# bat_mini_drby_2018.net
KiCad netlist of a schematic drawn in EAGLE
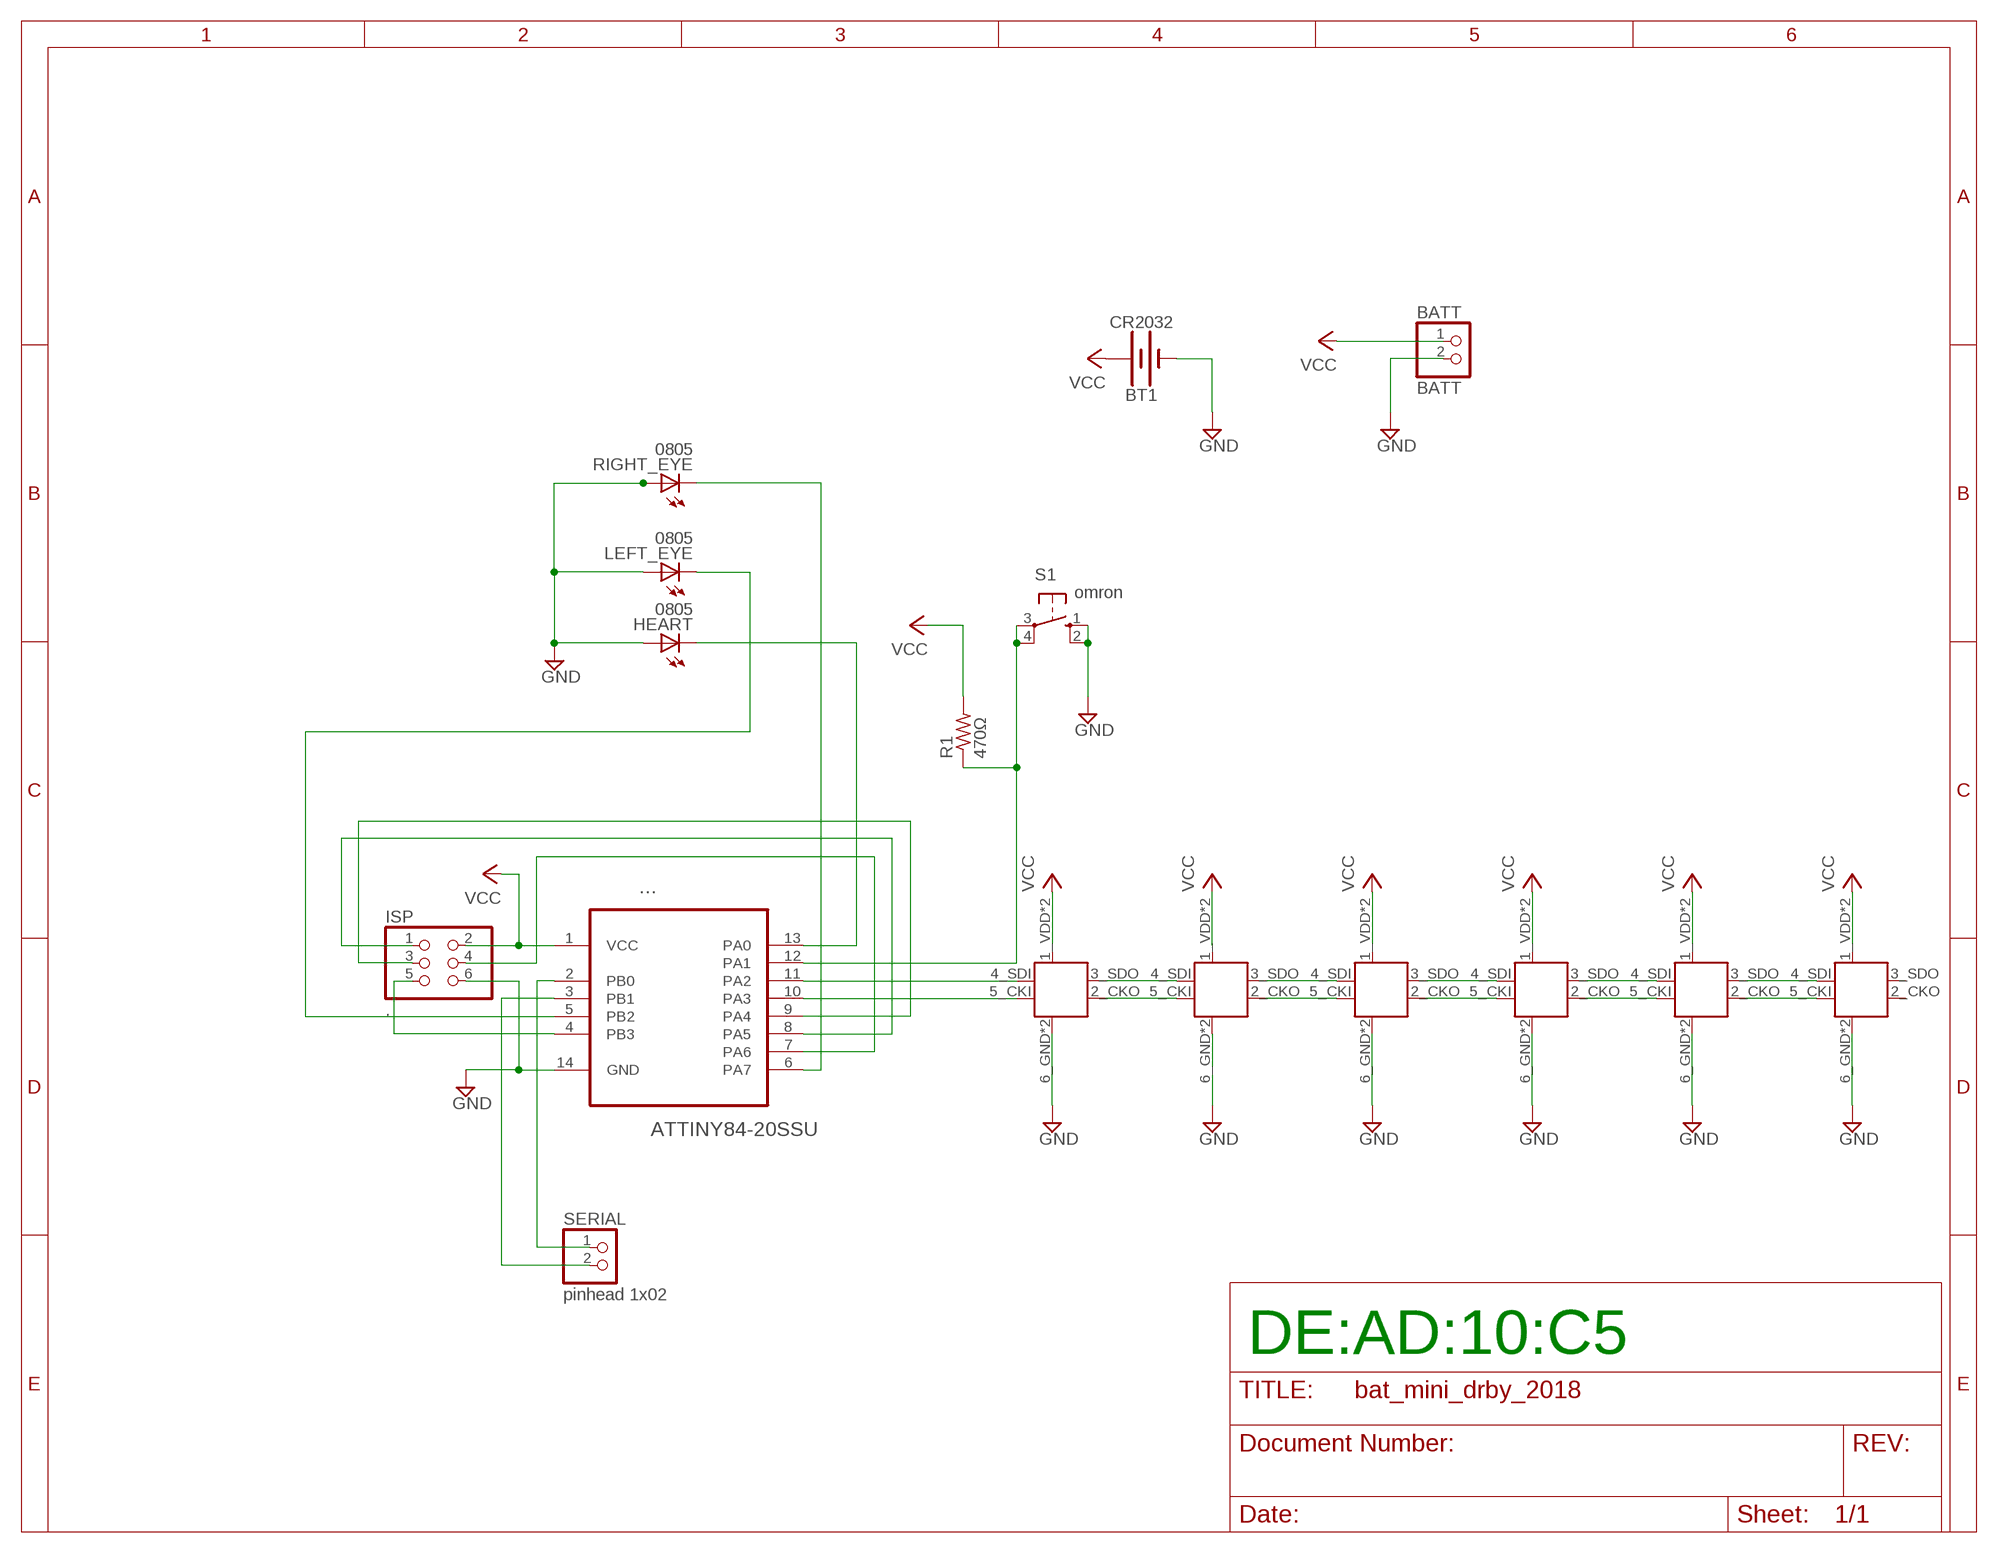
[diagram p0: schematic, sheet 1]

(export (version "E")
  (design (tool "Eeschema 10.0.6"))
  (components
    (comp (ref "...")
      (value "ATTINY84-20SSU")
      (footprint "eagle-import:SOIC127P600X175-14N")
      (libsource (lib "eagle-import") (part "ATTINY84-20SSU"))
    )
    (comp (ref "BATT")
      (value "BATT")
      (footprint "eagle-import:1X02")
      (libsource (lib "eagle-import") (part "PINHD-1X2"))
    )
    (comp (ref "BT1")
      (value "CR2032")
      (footprint "eagle-import:BATTCON_20MM_4LEGS")
      (libsource (lib "eagle-import") (part "BATTERY-20MM_SMD_4LEGS"))
    )
    (comp (ref "HEART")
      (value "0805")
      (footprint "eagle-import:CHIP-LED0805")
      (libsource (lib "eagle-import") (part "LEDCHIP-LED0805"))
    )
    (comp (ref "ISP")
      (value ".")
      (footprint "eagle-import:2X03")
      (libsource (lib "eagle-import") (part "PINHD-2X3"))
    )
    (comp (ref "LEFT_EYE")
      (value "0805")
      (footprint "eagle-import:CHIP-LED0805")
      (libsource (lib "eagle-import") (part "LEDCHIP-LED0805"))
    )
    (comp (ref "R1")
      (value "470Ω")
      (footprint "eagle-import:R0805")
      (libsource (lib "eagle-import") (part "R-US_R0805"))
    )
    (comp (ref "RIGHT_EYE")
      (value "0805")
      (footprint "eagle-import:CHIP-LED0805")
      (libsource (lib "eagle-import") (part "LEDCHIP-LED0805"))
    )
    (comp (ref "S1")
      (value "omron")
      (footprint "eagle-import:B3F-10XX")
      (fields (field (name "MPN") "B3F-1000"))
      (libsource (lib "eagle-import") (part "10-XX"))
    )
    (comp (ref "SERIAL")
      (value "pinhead 1x02")
      (footprint "eagle-import:1X02")
      (libsource (lib "eagle-import") (part "PINHD-1X2"))
    )
    (comp (ref "U$4")
      (value "APA102")
      (footprint "eagle-import:APA102-2020")
      (libsource (lib "eagle-import") (part "APA102"))
    )
    (comp (ref "U$8")
      (value "APA102")
      (footprint "eagle-import:APA102-2020")
      (libsource (lib "eagle-import") (part "APA102"))
    )
    (comp (ref "U$9")
      (value "APA102")
      (footprint "eagle-import:APA102-2020")
      (libsource (lib "eagle-import") (part "APA102"))
    )
    (comp (ref "U$10")
      (value "APA102")
      (footprint "eagle-import:APA102-2020")
      (libsource (lib "eagle-import") (part "APA102"))
    )
    (comp (ref "U$11")
      (value "APA102")
      (footprint "eagle-import:APA102-2020")
      (libsource (lib "eagle-import") (part "APA102"))
    )
    (comp (ref "U$12")
      (value "APA102")
      (footprint "eagle-import:APA102-2020")
      (libsource (lib "eagle-import") (part "APA102"))
    )
  )
  (nets
    (net (code "1") (name "GND") (class "Default")
      (node (ref "...") (pin "14") (pinfunction "GND_14") (pintype "passive"))
      (node (ref "BATT") (pin "2") (pinfunction "2_2") (pintype "passive"))
      (node (ref "BT1") (pin "NEGATIVE") (pinfunction "-_NEGATIVE") (pintype "power_in"))
      (node (ref "HEART") (pin "A") (pinfunction "A_A") (pintype "passive"))
      (node (ref "ISP") (pin "6") (pinfunction "6_6") (pintype "passive"))
      (node (ref "LEFT_EYE") (pin "A") (pinfunction "A_A") (pintype "passive"))
      (node (ref "RIGHT_EYE") (pin "A") (pinfunction "A_A") (pintype "passive"))
      (node (ref "S1") (pin "1") (pinfunction "S_1") (pintype "passive"))
      (node (ref "S1") (pin "2") (pinfunction "S1_2") (pintype "passive"))
      (node (ref "U$10") (pin "6_GND") (pinfunction "GND_6_GND") (pintype "power_in"))
      (node (ref "U$10") (pin "GNDPAD") (pinfunction "GND_GNDPAD") (pintype "power_in"))
      (node (ref "U$11") (pin "6_GND") (pinfunction "GND_6_GND") (pintype "power_in"))
      (node (ref "U$11") (pin "GNDPAD") (pinfunction "GND_GNDPAD") (pintype "power_in"))
      (node (ref "U$12") (pin "6_GND") (pinfunction "GND_6_GND") (pintype "power_in"))
      (node (ref "U$12") (pin "GNDPAD") (pinfunction "GND_GNDPAD") (pintype "power_in"))
      (node (ref "U$4") (pin "6_GND") (pinfunction "GND_6_GND") (pintype "power_in"))
      (node (ref "U$4") (pin "GNDPAD") (pinfunction "GND_GNDPAD") (pintype "power_in"))
      (node (ref "U$8") (pin "6_GND") (pinfunction "GND_6_GND") (pintype "power_in"))
      (node (ref "U$8") (pin "GNDPAD") (pinfunction "GND_GNDPAD") (pintype "power_in"))
      (node (ref "U$9") (pin "6_GND") (pinfunction "GND_6_GND") (pintype "power_in"))
      (node (ref "U$9") (pin "GNDPAD") (pinfunction "GND_GNDPAD") (pintype "power_in"))
    )
    (net (code "2") (name "Net-(...-PA0)") (class "Default")
      (node (ref "...") (pin "13") (pinfunction "PA0_13") (pintype "bidirectional"))
      (node (ref "HEART") (pin "C") (pinfunction "C_C") (pintype "passive"))
    )
    (net (code "3") (name "Net-(...-PA1)") (class "Default")
      (node (ref "...") (pin "12") (pinfunction "PA1_12") (pintype "bidirectional"))
      (node (ref "R1") (pin "1") (pinfunction "1_1") (pintype "passive"))
      (node (ref "S1") (pin "3") (pinfunction "P_3") (pintype "passive"))
      (node (ref "S1") (pin "4") (pinfunction "P1_4") (pintype "passive"))
    )
    (net (code "4") (name "Net-(...-PA2)") (class "Default")
      (node (ref "...") (pin "11") (pinfunction "PA2_11") (pintype "bidirectional"))
      (node (ref "U$4") (pin "4_SDI") (pinfunction "SDI_4_SDI") (pintype "input"))
    )
    (net (code "5") (name "Net-(...-PA3)") (class "Default")
      (node (ref "...") (pin "10") (pinfunction "PA3_10") (pintype "bidirectional"))
      (node (ref "U$4") (pin "5_CKI") (pinfunction "CKI_5_CKI") (pintype "input"))
    )
    (net (code "6") (name "Net-(...-PA4)") (class "Default")
      (node (ref "...") (pin "9") (pinfunction "PA4_9") (pintype "bidirectional"))
      (node (ref "ISP") (pin "3") (pinfunction "3_3") (pintype "passive"))
    )
    (net (code "7") (name "Net-(...-PA5)") (class "Default")
      (node (ref "...") (pin "8") (pinfunction "PA5_8") (pintype "bidirectional"))
      (node (ref "ISP") (pin "1") (pinfunction "1_1") (pintype "passive"))
    )
    (net (code "8") (name "Net-(...-PA6)") (class "Default")
      (node (ref "...") (pin "7") (pinfunction "PA6_7") (pintype "bidirectional"))
      (node (ref "ISP") (pin "4") (pinfunction "4_4") (pintype "passive"))
    )
    (net (code "9") (name "Net-(...-PA7)") (class "Default")
      (node (ref "...") (pin "6") (pinfunction "PA7_6") (pintype "bidirectional"))
      (node (ref "RIGHT_EYE") (pin "C") (pinfunction "C_C") (pintype "passive"))
    )
    (net (code "10") (name "Net-(...-PB0)") (class "Default")
      (node (ref "...") (pin "2") (pinfunction "PB0_2") (pintype "bidirectional"))
      (node (ref "SERIAL") (pin "1") (pinfunction "1_1") (pintype "passive"))
    )
    (net (code "11") (name "Net-(...-PB1)") (class "Default")
      (node (ref "...") (pin "3") (pinfunction "PB1_3") (pintype "bidirectional"))
      (node (ref "SERIAL") (pin "2") (pinfunction "2_2") (pintype "passive"))
    )
    (net (code "12") (name "Net-(...-PB2)") (class "Default")
      (node (ref "...") (pin "5") (pinfunction "PB2_5") (pintype "bidirectional"))
      (node (ref "LEFT_EYE") (pin "C") (pinfunction "C_C") (pintype "passive"))
    )
    (net (code "13") (name "Net-(...-PB3)") (class "Default")
      (node (ref "...") (pin "4") (pinfunction "PB3_4") (pintype "bidirectional"))
      (node (ref "ISP") (pin "5") (pinfunction "5_5") (pintype "passive"))
    )
    (net (code "14") (name "Net-(U$4-CKO)") (class "Default")
      (node (ref "U$4") (pin "2_CKO") (pinfunction "CKO_2_CKO") (pintype "output"))
      (node (ref "U$8") (pin "5_CKI") (pinfunction "CKI_5_CKI") (pintype "input"))
    )
    (net (code "15") (name "Net-(U$4-SDO)") (class "Default")
      (node (ref "U$4") (pin "3_SDO") (pinfunction "SDO_3_SDO") (pintype "output"))
      (node (ref "U$8") (pin "4_SDI") (pinfunction "SDI_4_SDI") (pintype "input"))
    )
    (net (code "16") (name "Net-(U$8-CKO)") (class "Default")
      (node (ref "U$8") (pin "2_CKO") (pinfunction "CKO_2_CKO") (pintype "output"))
      (node (ref "U$9") (pin "5_CKI") (pinfunction "CKI_5_CKI") (pintype "input"))
    )
    (net (code "17") (name "Net-(U$8-SDO)") (class "Default")
      (node (ref "U$8") (pin "3_SDO") (pinfunction "SDO_3_SDO") (pintype "output"))
      (node (ref "U$9") (pin "4_SDI") (pinfunction "SDI_4_SDI") (pintype "input"))
    )
    (net (code "18") (name "Net-(U$10-CKI)") (class "Default")
      (node (ref "U$10") (pin "5_CKI") (pinfunction "CKI_5_CKI") (pintype "input"))
      (node (ref "U$9") (pin "2_CKO") (pinfunction "CKO_2_CKO") (pintype "output"))
    )
    (net (code "19") (name "Net-(U$10-CKO)") (class "Default")
      (node (ref "U$10") (pin "2_CKO") (pinfunction "CKO_2_CKO") (pintype "output"))
      (node (ref "U$11") (pin "5_CKI") (pinfunction "CKI_5_CKI") (pintype "input"))
    )
    (net (code "20") (name "Net-(U$10-SDI)") (class "Default")
      (node (ref "U$10") (pin "4_SDI") (pinfunction "SDI_4_SDI") (pintype "input"))
      (node (ref "U$9") (pin "3_SDO") (pinfunction "SDO_3_SDO") (pintype "output"))
    )
    (net (code "21") (name "Net-(U$10-SDO)") (class "Default")
      (node (ref "U$10") (pin "3_SDO") (pinfunction "SDO_3_SDO") (pintype "output"))
      (node (ref "U$11") (pin "4_SDI") (pinfunction "SDI_4_SDI") (pintype "input"))
    )
    (net (code "22") (name "Net-(U$11-CKO)") (class "Default")
      (node (ref "U$11") (pin "2_CKO") (pinfunction "CKO_2_CKO") (pintype "output"))
      (node (ref "U$12") (pin "5_CKI") (pinfunction "CKI_5_CKI") (pintype "input"))
    )
    (net (code "23") (name "Net-(U$11-SDO)") (class "Default")
      (node (ref "U$11") (pin "3_SDO") (pinfunction "SDO_3_SDO") (pintype "output"))
      (node (ref "U$12") (pin "4_SDI") (pinfunction "SDI_4_SDI") (pintype "input"))
    )
    (net (code "24") (name "VCC") (class "Default")
      (node (ref "...") (pin "1") (pinfunction "VCC_1") (pintype "power_in"))
      (node (ref "BATT") (pin "1") (pinfunction "1_1") (pintype "passive"))
      (node (ref "BT1") (pin "POSITIVE@1") (pinfunction "+_POSITIVE@1") (pintype "power_in"))
      (node (ref "BT1") (pin "POSITIVE@2") (pinfunction "+_POSITIVE@2") (pintype "power_in"))
      (node (ref "BT1") (pin "POSITIVE@3") (pinfunction "+_POSITIVE@3") (pintype "power_in"))
      (node (ref "BT1") (pin "POSITIVE@4") (pinfunction "+_POSITIVE@4") (pintype "power_in"))
      (node (ref "ISP") (pin "2") (pinfunction "2_2") (pintype "passive"))
      (node (ref "R1") (pin "2") (pinfunction "2_2") (pintype "passive"))
      (node (ref "U$10") (pin "1_VDD") (pinfunction "VCC_1_VDD") (pintype "power_in"))
      (node (ref "U$10") (pin "VDDPAD") (pinfunction "VCC_VDDPAD") (pintype "power_in"))
      (node (ref "U$11") (pin "1_VDD") (pinfunction "VCC_1_VDD") (pintype "power_in"))
      (node (ref "U$11") (pin "VDDPAD") (pinfunction "VCC_VDDPAD") (pintype "power_in"))
      (node (ref "U$12") (pin "1_VDD") (pinfunction "VCC_1_VDD") (pintype "power_in"))
      (node (ref "U$12") (pin "VDDPAD") (pinfunction "VCC_VDDPAD") (pintype "power_in"))
      (node (ref "U$4") (pin "1_VDD") (pinfunction "VCC_1_VDD") (pintype "power_in"))
      (node (ref "U$4") (pin "VDDPAD") (pinfunction "VCC_VDDPAD") (pintype "power_in"))
      (node (ref "U$8") (pin "1_VDD") (pinfunction "VCC_1_VDD") (pintype "power_in"))
      (node (ref "U$8") (pin "VDDPAD") (pinfunction "VCC_VDDPAD") (pintype "power_in"))
      (node (ref "U$9") (pin "1_VDD") (pinfunction "VCC_1_VDD") (pintype "power_in"))
      (node (ref "U$9") (pin "VDDPAD") (pinfunction "VCC_VDDPAD") (pintype "power_in"))
    )
    (net (code "25") (name "unconnected-(U$12-CKO-Pad2_CKO)") (class "Default")
      (node (ref "U$12") (pin "2_CKO") (pinfunction "CKO_2_CKO") (pintype "output"))
    )
    (net (code "26") (name "unconnected-(U$12-SDO-Pad3_SDO)") (class "Default")
      (node (ref "U$12") (pin "3_SDO") (pinfunction "SDO_3_SDO") (pintype "output"))
    )
  )
)
